# SCH_Balansir-280-V2_2023-08-31.net
KiCad netlist of a schematic drawn in EasyEDA
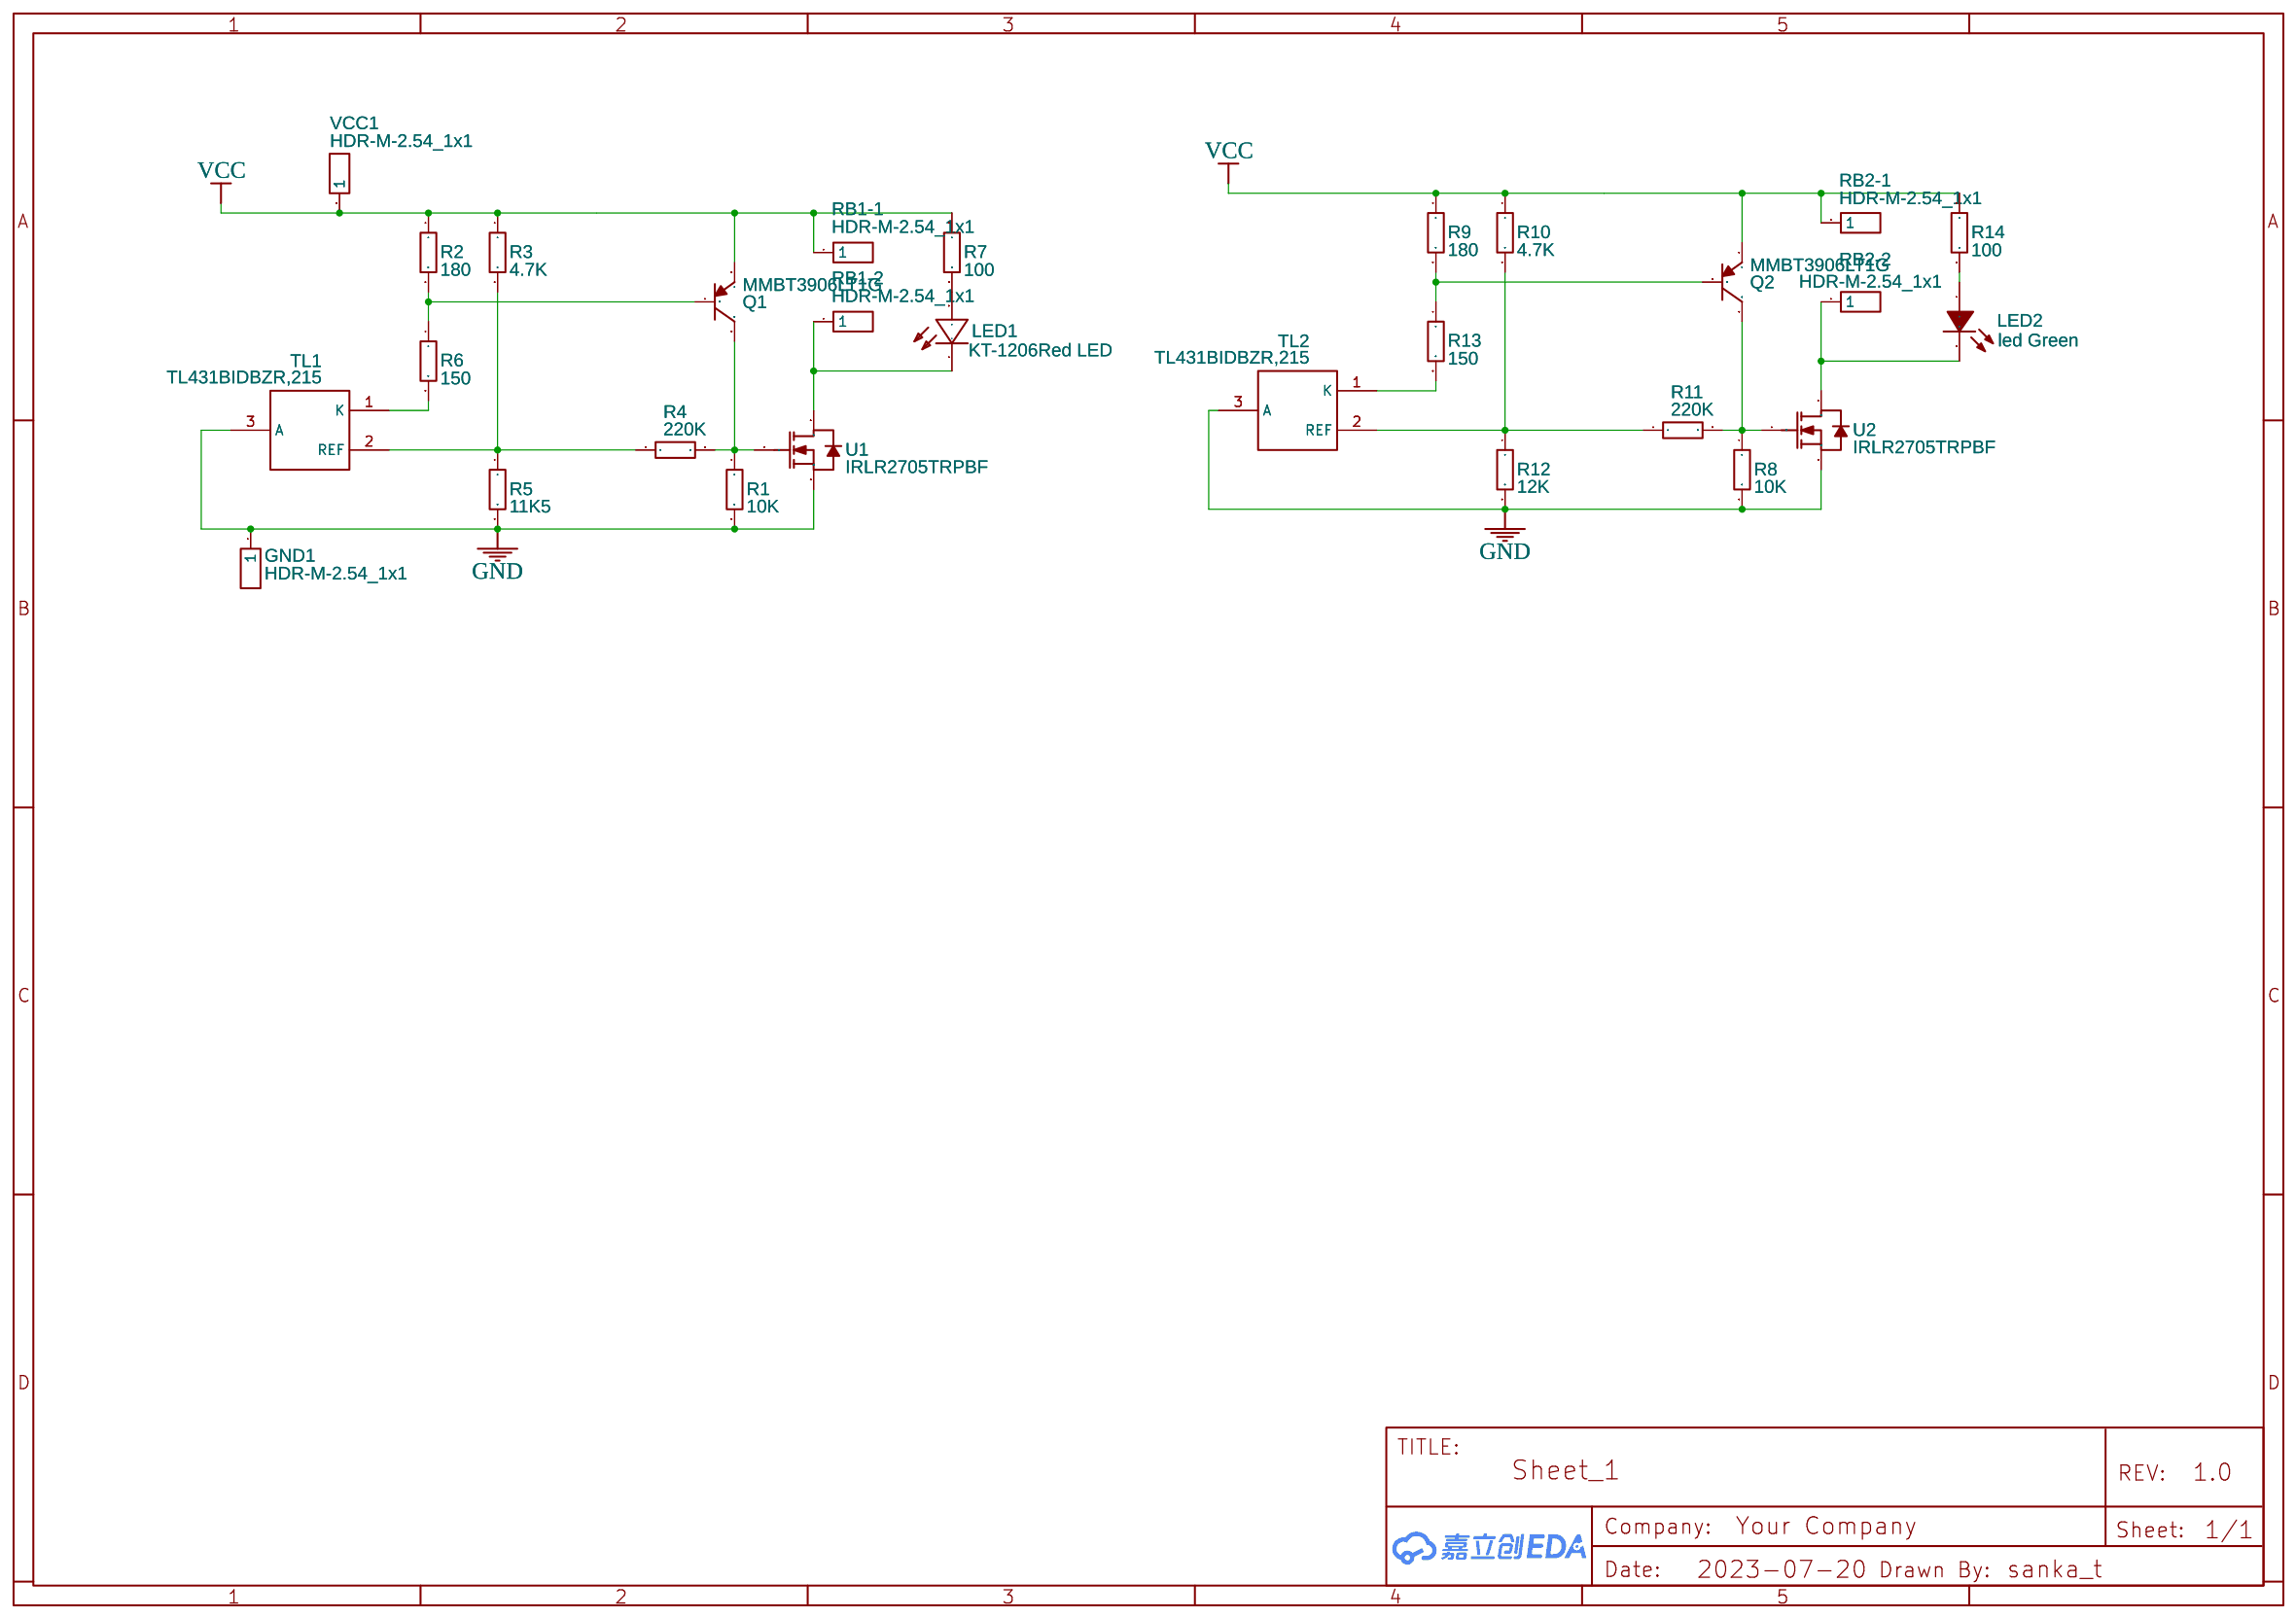
[diagram p0: schematic sheet]

(export (version "E")
  (design (tool "Eeschema 10.0.6"))
  (components
    (comp (ref "GND1") (value "HDR-M-2.54_1x1") (libsource (lib "") (part "HDR-M-2.54_1x1_1")))
    (comp (ref "LED1")
      (value "led Green")
      (fields (field (name "Manufacturer") "KENTO"))
      (libsource (lib "") (part "led Green"))
    )
    (comp (ref "LED2")
      (value "KT-1206Red LED")
      (fields (field (name "Manufacturer") "KENTO"))
      (libsource (lib "") (part "KT-1206Red LED"))
    )
    (comp (ref "Q1")
      (value "MMBT3906LT1G")
      (fields (field (name "Manufacturer") "ON"))
      (libsource (lib "") (part "MMBT3906LT1G"))
    )
    (comp (ref "Q2")
      (value "MMBT3906LT1G")
      (fields (field (name "Manufacturer") "ON"))
      (libsource (lib "") (part "MMBT3906LT1G"))
    )
    (comp (ref "R1")
      (value "10K")
      (fields (field (name "Manufacturer Part") "RC1206JR-0710KL") (field (name "Manufacturer") "YAGEO"))
      (libsource (lib "") (part "RC1206JR-0710KL"))
    )
    (comp (ref "R2")
      (value "180")
      (fields (field (name "Manufacturer Part") "RC1206JR-07180RL") (field (name "Manufacturer") "YAGEO"))
      (libsource (lib "") (part "RC1206JR-07180RL"))
    )
    (comp (ref "R3")
      (value "4.7K")
      (fields (field (name "Manufacturer Part") "RC1206JR-074K7L") (field (name "Manufacturer") "YAGEO"))
      (libsource (lib "") (part "RC1206JR-074K7L"))
    )
    (comp (ref "R4")
      (value "220K")
      (fields (field (name "Manufacturer Part") "RC1206JR-07220KL") (field (name "Manufacturer") "YAGEO"))
      (libsource (lib "") (part "RC1206JR-07220KL"))
    )
    (comp (ref "R5")
      (value "11K5")
      (fields (field (name "Manufacturer Part") "RC1206JR-0711KL") (field (name "Manufacturer") "YAGEO"))
      (libsource (lib "") (part "RC1206JR-0711KL"))
    )
    (comp (ref "R6")
      (value "150")
      (fields (field (name "Manufacturer Part") "RC1206JR-07150RL") (field (name "Manufacturer") "YAGEO"))
      (libsource (lib "") (part "RC1206JR-07150RL"))
    )
    (comp (ref "R7")
      (value "100")
      (fields (field (name "Manufacturer Part") "RC1206JR-07100RL") (field (name "Manufacturer") "YAGEO"))
      (libsource (lib "") (part "RC1206JR-07100RL"))
    )
    (comp (ref "R8")
      (value "10K")
      (fields (field (name "Manufacturer Part") "RC1206JR-0710KL") (field (name "Manufacturer") "YAGEO"))
      (libsource (lib "") (part "RC1206JR-0710KL"))
    )
    (comp (ref "R9")
      (value "180")
      (fields (field (name "Manufacturer Part") "RC1206JR-07180RL") (field (name "Manufacturer") "YAGEO"))
      (libsource (lib "") (part "RC1206JR-07180RL"))
    )
    (comp (ref "R10")
      (value "4.7K")
      (fields (field (name "Manufacturer Part") "RC1206JR-074K7L") (field (name "Manufacturer") "YAGEO"))
      (libsource (lib "") (part "RC1206JR-074K7L"))
    )
    (comp (ref "R11")
      (value "220K")
      (fields (field (name "Manufacturer Part") "RC1206JR-07220KL") (field (name "Manufacturer") "YAGEO"))
      (libsource (lib "") (part "RC1206JR-07220KL"))
    )
    (comp (ref "R12")
      (value "12K")
      (fields (field (name "Manufacturer Part") "RC1206JR-0711KL") (field (name "Manufacturer") "YAGEO"))
      (libsource (lib "") (part "RC1206JR-0711KL"))
    )
    (comp (ref "R13")
      (value "150")
      (fields (field (name "Manufacturer Part") "RC1206JR-07150RL") (field (name "Manufacturer") "YAGEO"))
      (libsource (lib "") (part "RC1206JR-07150RL"))
    )
    (comp (ref "R14")
      (value "100")
      (fields (field (name "Manufacturer Part") "RC1206JR-07100RL") (field (name "Manufacturer") "YAGEO"))
      (libsource (lib "") (part "RC1206JR-07100RL"))
    )
    (comp (ref "RB1-1") (value "HDR-M-2.54_1x1") (libsource (lib "") (part "HDR-M-2.54_1x1_2")))
    (comp (ref "RB1-2") (value "HDR-M-2.54_1x1") (libsource (lib "") (part "HDR-M-2.54_1x1_2")))
    (comp (ref "RB2-1") (value "HDR-M-2.54_1x1") (libsource (lib "") (part "HDR-M-2.54_1x1_3")))
    (comp (ref "RB2-2") (value "HDR-M-2.54_1x1") (libsource (lib "") (part "HDR-M-2.54_1x1_3")))
    (comp (ref "TL1")
      (value "TL431BIDBZR,215")
      (fields (field (name "Manufacturer") "Nexperia"))
      (libsource (lib "") (part "TL431BIDBZR,215"))
    )
    (comp (ref "TL2")
      (value "TL431BIDBZR,215")
      (fields (field (name "Manufacturer") "Nexperia"))
      (libsource (lib "") (part "TL431BIDBZR,215"))
    )
    (comp (ref "U1")
      (value "IRLR2705TRPBF")
      (fields (field (name "Manufacturer") "Infineon Technologies"))
      (libsource (lib "") (part "IRLR2705TRPBF"))
    )
    (comp (ref "U2")
      (value "IRLR2705TRPBF")
      (fields (field (name "Manufacturer") "Infineon Technologies"))
      (libsource (lib "") (part "IRLR2705TRPBF"))
    )
    (comp (ref "VCC1") (value "HDR-M-2.54_1x1") (libsource (lib "") (part "HDR-M-2.54_1x1")))
  )
  (nets
    (net (code "1") (name "GND") (class "Default")
      (node (ref "GND1") (pin "1") (pinfunction "1_1") (pintype "input"))
      (node (ref "R1") (pin "2") (pinfunction "2_2") (pintype "input"))
      (node (ref "R12") (pin "2") (pinfunction "2_2") (pintype "unspecified"))
      (node (ref "R5") (pin "2") (pinfunction "2_2") (pintype "unspecified"))
      (node (ref "R8") (pin "2") (pinfunction "2_2") (pintype "input"))
      (node (ref "TL1") (pin "3") (pinfunction "A_3") (pintype "unspecified"))
      (node (ref "TL2") (pin "3") (pinfunction "A_3") (pintype "unspecified"))
      (node (ref "U1") (pin "3") (pinfunction "S_3") (pintype "unspecified"))
      (node (ref "U2") (pin "3") (pinfunction "S_3") (pintype "unspecified"))
    )
    (net (code "2") (name "Net-(LED1-+)") (class "Default")
      (node (ref "LED1") (pin "2") (pinfunction "+_2") (pintype "unspecified"))
      (node (ref "R7") (pin "2") (pinfunction "2_2") (pintype "input"))
    )
    (net (code "3") (name "Net-(LED1--)") (class "Default")
      (node (ref "LED1") (pin "1") (pinfunction "-_1") (pintype "unspecified"))
      (node (ref "RB1-2") (pin "1") (pinfunction "1_1") (pintype "input"))
      (node (ref "U1") (pin "2") (pinfunction "D_2") (pintype "unspecified"))
    )
    (net (code "4") (name "Net-(LED2-A)") (class "Default")
      (node (ref "LED2") (pin "1") (pinfunction "A_1") (pintype "unspecified"))
      (node (ref "R14") (pin "2") (pinfunction "2_2") (pintype "input"))
    )
    (net (code "5") (name "Net-(LED2-K)") (class "Default")
      (node (ref "LED2") (pin "2") (pinfunction "K_2") (pintype "unspecified"))
      (node (ref "RB2-2") (pin "1") (pinfunction "1_1") (pintype "input"))
      (node (ref "U2") (pin "2") (pinfunction "D_2") (pintype "unspecified"))
    )
    (net (code "6") (name "Net-(Q1-B)") (class "Default")
      (node (ref "Q1") (pin "1") (pinfunction "B_1") (pintype "unspecified"))
      (node (ref "R2") (pin "2") (pinfunction "2_2") (pintype "input"))
      (node (ref "R6") (pin "1") (pinfunction "1_1") (pintype "input"))
    )
    (net (code "7") (name "Net-(Q1-C)") (class "Default")
      (node (ref "Q1") (pin "3") (pinfunction "C_3") (pintype "unspecified"))
      (node (ref "R1") (pin "1") (pinfunction "1_1") (pintype "input"))
      (node (ref "R4") (pin "2") (pinfunction "2_2") (pintype "input"))
      (node (ref "U1") (pin "1") (pinfunction "G_1") (pintype "unspecified"))
    )
    (net (code "8") (name "Net-(Q2-B)") (class "Default")
      (node (ref "Q2") (pin "1") (pinfunction "B_1") (pintype "unspecified"))
      (node (ref "R13") (pin "1") (pinfunction "1_1") (pintype "input"))
      (node (ref "R9") (pin "2") (pinfunction "2_2") (pintype "input"))
    )
    (net (code "9") (name "Net-(Q2-C)") (class "Default")
      (node (ref "Q2") (pin "3") (pinfunction "C_3") (pintype "unspecified"))
      (node (ref "R11") (pin "2") (pinfunction "2_2") (pintype "input"))
      (node (ref "R8") (pin "1") (pinfunction "1_1") (pintype "input"))
      (node (ref "U2") (pin "1") (pinfunction "G_1") (pintype "unspecified"))
    )
    (net (code "10") (name "Net-(TL1-K)") (class "Default")
      (node (ref "R6") (pin "2") (pinfunction "2_2") (pintype "input"))
      (node (ref "TL1") (pin "1") (pinfunction "K_1") (pintype "unspecified"))
    )
    (net (code "11") (name "Net-(TL1-REF)") (class "Default")
      (node (ref "R3") (pin "2") (pinfunction "2_2") (pintype "input"))
      (node (ref "R4") (pin "1") (pinfunction "1_1") (pintype "input"))
      (node (ref "R5") (pin "1") (pinfunction "1_1") (pintype "unspecified"))
      (node (ref "TL1") (pin "2") (pinfunction "REF_2") (pintype "unspecified"))
    )
    (net (code "12") (name "Net-(TL2-K)") (class "Default")
      (node (ref "R13") (pin "2") (pinfunction "2_2") (pintype "input"))
      (node (ref "TL2") (pin "1") (pinfunction "K_1") (pintype "unspecified"))
    )
    (net (code "13") (name "Net-(TL2-REF)") (class "Default")
      (node (ref "R10") (pin "2") (pinfunction "2_2") (pintype "input"))
      (node (ref "R11") (pin "1") (pinfunction "1_1") (pintype "input"))
      (node (ref "R12") (pin "1") (pinfunction "1_1") (pintype "unspecified"))
      (node (ref "TL2") (pin "2") (pinfunction "REF_2") (pintype "unspecified"))
    )
    (net (code "14") (name "VCC") (class "Default")
      (node (ref "Q1") (pin "2") (pinfunction "E_2") (pintype "unspecified"))
      (node (ref "Q2") (pin "2") (pinfunction "E_2") (pintype "unspecified"))
      (node (ref "R10") (pin "1") (pinfunction "1_1") (pintype "input"))
      (node (ref "R14") (pin "1") (pinfunction "1_1") (pintype "input"))
      (node (ref "R2") (pin "1") (pinfunction "1_1") (pintype "input"))
      (node (ref "R3") (pin "1") (pinfunction "1_1") (pintype "input"))
      (node (ref "R7") (pin "1") (pinfunction "1_1") (pintype "input"))
      (node (ref "R9") (pin "1") (pinfunction "1_1") (pintype "input"))
      (node (ref "RB1-1") (pin "1") (pinfunction "1_1") (pintype "input"))
      (node (ref "RB2-1") (pin "1") (pinfunction "1_1") (pintype "input"))
      (node (ref "VCC1") (pin "1") (pinfunction "1_1") (pintype "input"))
    )
  )
)
